# DM1098OAKW_LEVEL_SHIFT.net
KiCad netlist of a schematic drawn in Altium Designer
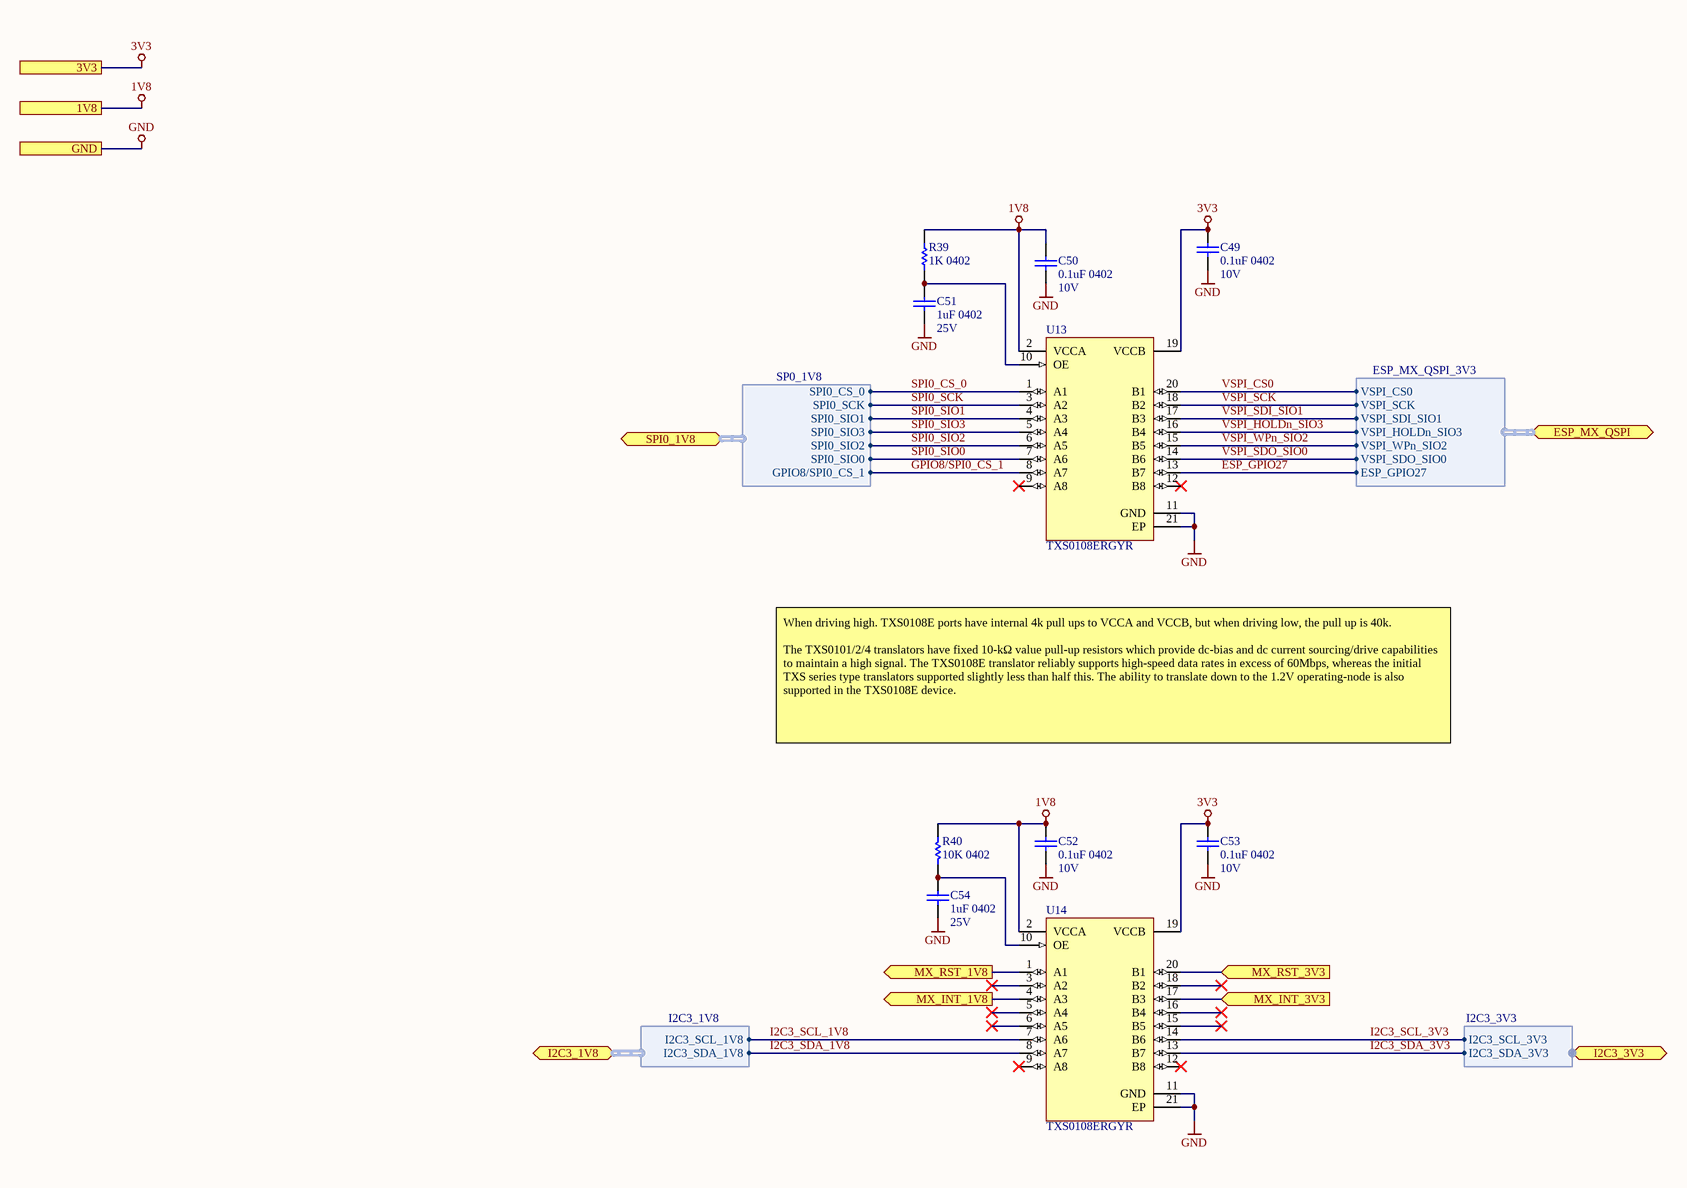
[diagram p0: DM1098OAKW_LEVEL_SHIFT.SchDoc]

(export (version "E")
  (design (tool "Eeschema 10.0.6"))
  (components
    (comp (ref "C49")
      (value "0.1uF 0402")
      (footprint "CAP_Altium_Vault_Generic:CAPC0402(1005)70_N")
      (description "CAP CER 0.1UF 10V X7R 0402 5%")
      (fields (field (name "TOLERANCE") "5%") (field (name "VOLTAGE RATING") "10V"))
      (libsource (lib "LuxonisMaster") (part "GRM155R71A104JA01D"))
    )
    (comp (ref "C50")
      (value "0.1uF 0402")
      (footprint "CAP_Altium_Vault_Generic:CAPC0402(1005)70_N")
      (description "CAP CER 0.1UF 10V X7R 0402 5%")
      (fields (field (name "TOLERANCE") "5%") (field (name "VOLTAGE RATING") "10V"))
      (libsource (lib "LuxonisMaster") (part "GRM155R71A104JA01D"))
    )
    (comp (ref "C51")
      (value "1uF 0402")
      (footprint "CAP_Altium_Vault_Generic:CAPC0402(1005)70_N")
      (description "CAP CER 1UF 25V X5R 0402 10%")
      (fields
        (field (name "TOLERANCE") "10%")
        (field (name "VOLTAGE") "25V")
        (field (name "VOLTAGE RATING") "25V")
      )
      (libsource (lib "LuxonisMaster") (part "GRM155R61E105KA12D"))
    )
    (comp (ref "C52")
      (value "0.1uF 0402")
      (footprint "CAP_Altium_Vault_Generic:CAPC0402(1005)70_N")
      (description "CAP CER 0.1UF 10V X7R 0402 5%")
      (fields (field (name "TOLERANCE") "5%") (field (name "VOLTAGE RATING") "10V"))
      (libsource (lib "LuxonisMaster") (part "GRM155R71A104JA01D"))
    )
    (comp (ref "C53")
      (value "0.1uF 0402")
      (footprint "CAP_Altium_Vault_Generic:CAPC0402(1005)70_N")
      (description "CAP CER 0.1UF 10V X7R 0402 5%")
      (fields (field (name "TOLERANCE") "5%") (field (name "VOLTAGE RATING") "10V"))
      (libsource (lib "LuxonisMaster") (part "GRM155R71A104JA01D"))
    )
    (comp (ref "C54")
      (value "1uF 0402")
      (footprint "CAP_Altium_Vault_Generic:CAPC0402(1005)70_N")
      (description "CAP CER 1UF 25V X5R 0402 10%")
      (fields
        (field (name "TOLERANCE") "10%")
        (field (name "VOLTAGE") "25V")
        (field (name "VOLTAGE RATING") "25V")
      )
      (libsource (lib "LuxonisMaster") (part "GRM155R61E105KA12D"))
    )
    (comp (ref "R39")
      (value "1K 0402")
      (footprint "RES_Altium_Vault_Generic:RESC0402(1005)_N")
      (fields (field (name "TOLERANCE") "1%"))
      (libsource (lib "LuxonisMaster") (part "RC0402FR-071KL"))
    )
    (comp (ref "R40")
      (value "10K 0402")
      (footprint "RES_Altium_Vault_Generic:RESC0402(1005)_N")
      (fields (field (name "TOLERANCE") "1%"))
      (libsource (lib "LuxonisMaster") (part "RC0402FR-1310KL"))
    )
    (comp (ref "U13")
      (value "TXS0108ERGYR")
      (footprint "LuxonisMaster:TXS0108ERGYR")
      (description "IC TRNSLTR BIDIRECTIONAL 20VQFN")
      (libsource (lib "LuxonisMaster") (part "TXS0108ERGYR"))
    )
    (comp (ref "U14")
      (value "TXS0108ERGYR")
      (footprint "LuxonisMaster:TXS0108ERGYR")
      (description "IC TRNSLTR BIDIRECTIONAL 20VQFN")
      (libsource (lib "LuxonisMaster") (part "TXS0108ERGYR"))
    )
  )
  (nets
    (net (code "5") (name "/ESP_GPIO27") (class "Default")
      (node (ref "U13") (pin "13") (pinfunction "B7_13") (pintype "bidirectional"))
    )
    (net (code "6") (name "/GPIO8{slash}SPI0_CS_1") (class "Default")
      (node (ref "U13") (pin "8") (pinfunction "A7_8") (pintype "bidirectional"))
    )
    (net (code "7") (name "/I2C3_SCL_1V8") (class "Default")
      (node (ref "U14") (pin "7") (pinfunction "A6_7") (pintype "bidirectional"))
    )
    (net (code "8") (name "/I2C3_SCL_3V3") (class "Default")
      (node (ref "U14") (pin "14") (pinfunction "B6_14") (pintype "bidirectional"))
    )
    (net (code "9") (name "/I2C3_SDA_1V8") (class "Default")
      (node (ref "U14") (pin "8") (pinfunction "A7_8") (pintype "bidirectional"))
    )
    (net (code "10") (name "/I2C3_SDA_3V3") (class "Default")
      (node (ref "U14") (pin "13") (pinfunction "B7_13") (pintype "bidirectional"))
    )
    (net (code "11") (name "/MX_INT_1V8") (class "Default")
      (node (ref "U14") (pin "4") (pinfunction "A3_4") (pintype "bidirectional"))
    )
    (net (code "12") (name "/MX_INT_3V3") (class "Default")
      (node (ref "U14") (pin "17") (pinfunction "B3_17") (pintype "bidirectional"))
    )
    (net (code "13") (name "/MX_RST_1V8") (class "Default")
      (node (ref "U14") (pin "1") (pinfunction "A1_1") (pintype "bidirectional"))
    )
    (net (code "14") (name "/MX_RST_3V3") (class "Default")
      (node (ref "U14") (pin "20") (pinfunction "B1_20") (pintype "bidirectional"))
    )
    (net (code "15") (name "/SPI0_CS_0") (class "Default")
      (node (ref "U13") (pin "1") (pinfunction "A1_1") (pintype "bidirectional"))
    )
    (net (code "16") (name "/SPI0_SCK") (class "Default")
      (node (ref "U13") (pin "3") (pinfunction "A2_3") (pintype "bidirectional"))
    )
    (net (code "17") (name "/SPI0_SIO0") (class "Default")
      (node (ref "U13") (pin "7") (pinfunction "A6_7") (pintype "bidirectional"))
    )
    (net (code "18") (name "/SPI0_SIO1") (class "Default")
      (node (ref "U13") (pin "4") (pinfunction "A3_4") (pintype "bidirectional"))
    )
    (net (code "19") (name "/SPI0_SIO2") (class "Default")
      (node (ref "U13") (pin "6") (pinfunction "A5_6") (pintype "bidirectional"))
    )
    (net (code "20") (name "/SPI0_SIO3") (class "Default")
      (node (ref "U13") (pin "5") (pinfunction "A4_5") (pintype "bidirectional"))
    )
    (net (code "21") (name "/VSPI_CS0") (class "Default")
      (node (ref "U13") (pin "20") (pinfunction "B1_20") (pintype "bidirectional"))
    )
    (net (code "22") (name "/VSPI_HOLDn_SIO3") (class "Default")
      (node (ref "U13") (pin "16") (pinfunction "B4_16") (pintype "bidirectional"))
    )
    (net (code "23") (name "/VSPI_SCK") (class "Default")
      (node (ref "U13") (pin "18") (pinfunction "B2_18") (pintype "bidirectional"))
    )
    (net (code "24") (name "/VSPI_SDI_SIO1") (class "Default")
      (node (ref "U13") (pin "17") (pinfunction "B3_17") (pintype "bidirectional"))
    )
    (net (code "25") (name "/VSPI_SDO_SIO0") (class "Default")
      (node (ref "U13") (pin "14") (pinfunction "B6_14") (pintype "bidirectional"))
    )
    (net (code "26") (name "/VSPI_WPn_SIO2") (class "Default")
      (node (ref "U13") (pin "15") (pinfunction "B5_15") (pintype "bidirectional"))
    )
    (net (code "31") (name "1V8") (class "Default")
      (node (ref "C50") (pin "2") (pinfunction "2_2") (pintype "passive"))
      (node (ref "C52") (pin "2") (pinfunction "2_2") (pintype "passive"))
      (node (ref "R39") (pin "2") (pinfunction "2_2") (pintype "passive"))
      (node (ref "R40") (pin "1") (pinfunction "1_1") (pintype "passive"))
      (node (ref "U13") (pin "2") (pinfunction "VCCA_2") (pintype "power_in"))
      (node (ref "U14") (pin "2") (pinfunction "VCCA_2") (pintype "power_in"))
    )
    (net (code "32") (name "3V3") (class "Default")
      (node (ref "C49") (pin "2") (pinfunction "2_2") (pintype "passive"))
      (node (ref "C53") (pin "2") (pinfunction "2_2") (pintype "passive"))
      (node (ref "U13") (pin "19") (pinfunction "VCCB_19") (pintype "power_in"))
      (node (ref "U14") (pin "19") (pinfunction "VCCB_19") (pintype "power_in"))
    )
    (net (code "33") (name "GND") (class "Default")
      (node (ref "C49") (pin "1") (pinfunction "1_1") (pintype "passive"))
      (node (ref "C50") (pin "1") (pinfunction "1_1") (pintype "passive"))
      (node (ref "C51") (pin "1") (pinfunction "1_1") (pintype "passive"))
      (node (ref "C52") (pin "1") (pinfunction "1_1") (pintype "passive"))
      (node (ref "C53") (pin "1") (pinfunction "1_1") (pintype "passive"))
      (node (ref "C54") (pin "1") (pinfunction "1_1") (pintype "passive"))
      (node (ref "U13") (pin "11") (pinfunction "GND_11") (pintype "power_in"))
      (node (ref "U13") (pin "21") (pinfunction "EP_21") (pintype "power_in"))
      (node (ref "U14") (pin "11") (pinfunction "GND_11") (pintype "power_in"))
      (node (ref "U14") (pin "21") (pinfunction "EP_21") (pintype "power_in"))
    )
    (net (code "34") (name "Net-(U13-OE)") (class "Default")
      (node (ref "C51") (pin "2") (pinfunction "2_2") (pintype "passive"))
      (node (ref "R39") (pin "1") (pinfunction "1_1") (pintype "passive"))
      (node (ref "U13") (pin "10") (pinfunction "OE_10") (pintype "input"))
    )
    (net (code "35") (name "Net-(U14-OE)") (class "Default")
      (node (ref "C54") (pin "2") (pinfunction "2_2") (pintype "passive"))
      (node (ref "R40") (pin "2") (pinfunction "2_2") (pintype "passive"))
      (node (ref "U14") (pin "10") (pinfunction "OE_10") (pintype "input"))
    )
    (net (code "36") (name "unconnected-(U13-A8-Pad9)") (class "Default")
      (node (ref "U13") (pin "9") (pinfunction "A8_9") (pintype "bidirectional+no_connect"))
    )
    (net (code "37") (name "unconnected-(U13-B8-Pad12)") (class "Default")
      (node (ref "U13") (pin "12") (pinfunction "B8_12") (pintype "bidirectional+no_connect"))
    )
    (net (code "38") (name "unconnected-(U14-A2-Pad3)") (class "Default")
      (node (ref "U14") (pin "3") (pinfunction "A2_3") (pintype "bidirectional+no_connect"))
    )
    (net (code "39") (name "unconnected-(U14-A4-Pad5)") (class "Default")
      (node (ref "U14") (pin "5") (pinfunction "A4_5") (pintype "bidirectional+no_connect"))
    )
    (net (code "40") (name "unconnected-(U14-A5-Pad6)") (class "Default")
      (node (ref "U14") (pin "6") (pinfunction "A5_6") (pintype "bidirectional+no_connect"))
    )
    (net (code "41") (name "unconnected-(U14-A8-Pad9)") (class "Default")
      (node (ref "U14") (pin "9") (pinfunction "A8_9") (pintype "bidirectional+no_connect"))
    )
    (net (code "42") (name "unconnected-(U14-B2-Pad18)") (class "Default")
      (node (ref "U14") (pin "18") (pinfunction "B2_18") (pintype "bidirectional+no_connect"))
    )
    (net (code "43") (name "unconnected-(U14-B4-Pad16)") (class "Default")
      (node (ref "U14") (pin "16") (pinfunction "B4_16") (pintype "bidirectional+no_connect"))
    )
    (net (code "44") (name "unconnected-(U14-B5-Pad15)") (class "Default")
      (node (ref "U14") (pin "15") (pinfunction "B5_15") (pintype "bidirectional+no_connect"))
    )
    (net (code "45") (name "unconnected-(U14-B8-Pad12)") (class "Default")
      (node (ref "U14") (pin "12") (pinfunction "B8_12") (pintype "bidirectional+no_connect"))
    )
  )
)
